# boost.net
KiCad netlist of a schematic drawn in Altium Designer
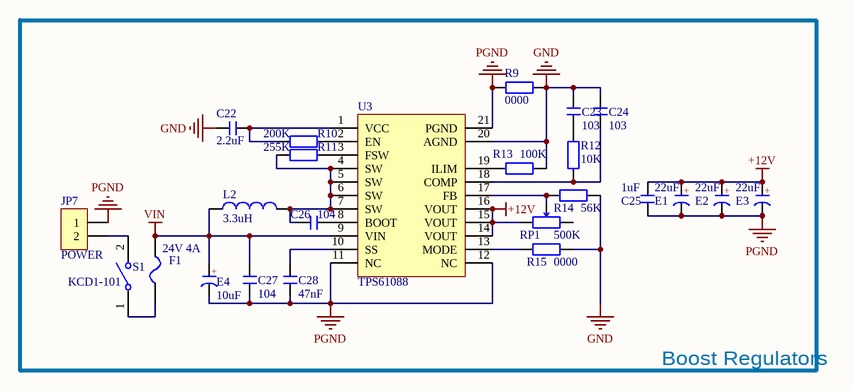
[diagram p0: boost.SchDoc]

(export (version "E")
  (design (tool "Eeschema 10.0.6"))
  (components
    (comp (ref "C22")
      (value "2.2uF")
      (footprint "C 0603_L")
      (description "无极性贴片电容")
      (fields (field (name "版权归属") "源创客"))
      (libsource (lib "3.1   - 电阻-电容-电感") (part "C"))
    )
    (comp (ref "C23")
      (value "103")
      (footprint "C 0603_L")
      (description "无极性贴片电容")
      (fields (field (name "版权归属") "源创客"))
      (libsource (lib "3.1   - 电阻-电容-电感") (part "C"))
    )
    (comp (ref "C24")
      (value "103")
      (footprint "C 0603_L")
      (description "无极性贴片电容")
      (fields (field (name "版权归属") "源创客"))
      (libsource (lib "3.1   - 电阻-电容-电感") (part "C"))
    )
    (comp (ref "C25")
      (value "1uF")
      (footprint "C 0603_L")
      (description "无极性贴片电容")
      (fields (field (name "版权归属") "源创客"))
      (libsource (lib "3.1   - 电阻-电容-电感") (part "C"))
    )
    (comp (ref "C26")
      (value "104")
      (footprint "C 0603_L")
      (description "无极性贴片电容")
      (fields (field (name "版权归属") "源创客"))
      (libsource (lib "3.1   - 电阻-电容-电感") (part "C"))
    )
    (comp (ref "C27")
      (value "104")
      (footprint "C 0603_L")
      (description "无极性贴片电容")
      (fields (field (name "版权归属") "源创客"))
      (libsource (lib "3.1   - 电阻-电容-电感") (part "C"))
    )
    (comp (ref "C28")
      (value "47nF")
      (footprint "C 0603_L")
      (description "无极性贴片电容")
      (fields (field (name "版权归属") "源创客"))
      (libsource (lib "3.1   - 电阻-电容-电感") (part "C"))
    )
    (comp (ref "E1")
      (value "22uF")
      (footprint "CD A(3216)")
      (description "贴片钽电容")
      (fields (field (name "版权归属") "源创客"))
      (libsource (lib "3.1   - 电阻-电容-电感") (part "C-CD"))
    )
    (comp (ref "E2")
      (value "22uF")
      (footprint "CD A(3216)")
      (description "贴片钽电容")
      (fields (field (name "版权归属") "源创客"))
      (libsource (lib "3.1   - 电阻-电容-电感") (part "C-CD"))
    )
    (comp (ref "E3")
      (value "22uF")
      (footprint "CD A(3216)")
      (description "贴片钽电容")
      (fields (field (name "版权归属") "源创客"))
      (libsource (lib "3.1   - 电阻-电容-电感") (part "C-CD"))
    )
    (comp (ref "E4")
      (value "10uF")
      (footprint "CD A(3216)")
      (description "贴片钽电容")
      (fields (field (name "版权归属") "源创客"))
      (libsource (lib "3.1   - 电阻-电容-电感") (part "C-CD"))
    )
    (comp (ref "F1")
      (value "24V 4A")
      (footprint "FU 1206")
      (description "贴片保险丝")
      (fields (field (name "版权归属") "源创客"))
      (libsource (lib "10.1 - 保险丝-晶振") (part "FU"))
    )
    (comp (ref "JP7")
      (value "POWER")
      (footprint "KF301-5.0-2P")
      (description "2P接插件")
      (fields (field (name "版权归属") "源创客"))
      (libsource (lib "4.10 - 接插件-脚距5.08") (part "Header 2"))
    )
    (comp (ref "L2")
      (value "3.3uH")
      (footprint "CDRH127")
      (description "Inductor")
      (fields (field (name "PUBLISHER") "Altium Limited"))
      (libsource (lib "Miscellaneous Devices") (part "Inductor"))
    )
    (comp (ref "R9")
      (value "0000")
      (footprint "R 0603_L")
      (description "贴片电阻")
      (fields (field (name "版权归属") "源创客"))
      (libsource (lib "3.1   - 电阻-电容-电感") (part "R"))
    )
    (comp (ref "R10")
      (value "200K")
      (footprint "R 0603_L")
      (description "贴片电阻")
      (fields (field (name "版权归属") "源创客"))
      (libsource (lib "3.1   - 电阻-电容-电感") (part "R"))
    )
    (comp (ref "R11")
      (value "255K")
      (footprint "R 0603_L")
      (description "贴片电阻")
      (fields (field (name "版权归属") "源创客"))
      (libsource (lib "3.1   - 电阻-电容-电感") (part "R"))
    )
    (comp (ref "R12")
      (value "10K")
      (footprint "R 0603_L")
      (description "贴片电阻")
      (fields (field (name "版权归属") "源创客"))
      (libsource (lib "3.1   - 电阻-电容-电感") (part "R"))
    )
    (comp (ref "R13")
      (value "100K")
      (footprint "R 0603_L")
      (description "贴片电阻")
      (fields (field (name "版权归属") "源创客"))
      (libsource (lib "3.1   - 电阻-电容-电感") (part "R"))
    )
    (comp (ref "R14")
      (value "56K")
      (footprint "R 0603_L")
      (description "贴片电阻")
      (fields (field (name "版权归属") "源创客"))
      (libsource (lib "3.1   - 电阻-电容-电感") (part "R"))
    )
    (comp (ref "R15")
      (value "0000")
      (footprint "R 0603_L")
      (description "贴片电阻")
      (fields (field (name "版权归属") "源创客"))
      (libsource (lib "3.1   - 电阻-电容-电感") (part "R"))
    )
    (comp (ref "RP1")
      (value "500K")
      (footprint "3296W")
      (description "插件单联电位器")
      (fields (field (name "版权归属") "源创客"))
      (libsource (lib "3.1   - 电阻-电容-电感") (part "RP-ID"))
    )
    (comp (ref "S1")
      (value "KCD1-101")
      (footprint "KCD1-101")
      (description "1路单刀船型开关")
      (fields (field (name "版权归属") "源创客"))
      (libsource (lib "5.1   - 按键-开关") (part "KCD1-101"))
    )
    (comp (ref "U3")
      (value "TPS61088")
      (footprint "S-PVQFN-N20")
      (libsource (lib "TPS61088") (part "TPS61088"))
    )
  )
  (nets
    (net (code "1") (name "+12V") (class "Default")
      (node (ref "C25") (pin "2") (pinfunction "2_2") (pintype "passive"))
      (node (ref "E1") (pin "1") (pinfunction "A_1") (pintype "passive"))
      (node (ref "E2") (pin "1") (pinfunction "A_1") (pintype "passive"))
      (node (ref "E3") (pin "1") (pinfunction "A_1") (pintype "passive"))
      (node (ref "RP1") (pin "1") (pinfunction "1_1") (pintype "passive"))
      (node (ref "U3") (pin "14") (pinfunction "VOUT_14") (pintype "passive"))
      (node (ref "U3") (pin "15") (pinfunction "VOUT_15") (pintype "passive"))
      (node (ref "U3") (pin "16") (pinfunction "VOUT_16") (pintype "passive"))
    )
    (net (code "2") (name "GND") (class "Default")
      (node (ref "C22") (pin "2") (pinfunction "2_2") (pintype "passive"))
      (node (ref "C23") (pin "2") (pinfunction "2_2") (pintype "passive"))
      (node (ref "C24") (pin "2") (pinfunction "2_2") (pintype "passive"))
      (node (ref "R13") (pin "2") (pinfunction "2_2") (pintype "passive"))
      (node (ref "R14") (pin "1") (pinfunction "1_1") (pintype "passive"))
      (node (ref "R15") (pin "2") (pinfunction "2_2") (pintype "passive"))
      (node (ref "R9") (pin "2") (pinfunction "2_2") (pintype "passive"))
      (node (ref "U3") (pin "20") (pinfunction "AGND_20") (pintype "passive"))
    )
    (net (code "3") (name "Net-(C23-Pad1)") (class "Default")
      (node (ref "C23") (pin "1") (pinfunction "1_1") (pintype "passive"))
      (node (ref "R12") (pin "2") (pinfunction "2_2") (pintype "passive"))
    )
    (net (code "4") (name "Net-(C26-Pad2)") (class "Default")
      (node (ref "C26") (pin "2") (pinfunction "2_2") (pintype "passive"))
      (node (ref "L2") (pin "2") (pinfunction "2_2") (pintype "passive"))
      (node (ref "R11") (pin "2") (pinfunction "2_2") (pintype "passive"))
      (node (ref "U3") (pin "4") (pinfunction "SW_4") (pintype "passive"))
      (node (ref "U3") (pin "5") (pinfunction "SW_5") (pintype "passive"))
      (node (ref "U3") (pin "6") (pinfunction "SW_6") (pintype "passive"))
      (node (ref "U3") (pin "7") (pinfunction "SW_7") (pintype "passive"))
    )
    (net (code "5") (name "Net-(F1-Pad1)") (class "Default")
      (node (ref "F1") (pin "1") (pinfunction "1_1") (pintype "passive"))
      (node (ref "S1") (pin "1") (pinfunction "1_1") (pintype "passive"))
    )
    (net (code "6") (name "Net-(JP7-Pad2)") (class "Default")
      (node (ref "JP7") (pin "2") (pinfunction "2_2") (pintype "passive"))
      (node (ref "S1") (pin "2") (pinfunction "2_2") (pintype "passive"))
    )
    (net (code "7") (name "Net-(U3-BOOT)") (class "Default")
      (node (ref "C26") (pin "1") (pinfunction "1_1") (pintype "passive"))
      (node (ref "U3") (pin "8") (pinfunction "BOOT_8") (pintype "passive"))
    )
    (net (code "8") (name "Net-(U3-COMP)") (class "Default")
      (node (ref "C24") (pin "1") (pinfunction "1_1") (pintype "passive"))
      (node (ref "R12") (pin "1") (pinfunction "1_1") (pintype "passive"))
      (node (ref "U3") (pin "18") (pinfunction "COMP_18") (pintype "passive"))
    )
    (net (code "9") (name "Net-(U3-EN)") (class "Default")
      (node (ref "R10") (pin "1") (pinfunction "1_1") (pintype "passive"))
      (node (ref "U3") (pin "2") (pinfunction "EN_2") (pintype "passive"))
    )
    (net (code "10") (name "Net-(U3-FB)") (class "Default")
      (node (ref "R14") (pin "2") (pinfunction "2_2") (pintype "passive"))
      (node (ref "RP1") (pin "2") (pinfunction "2_2") (pintype "passive"))
      (node (ref "U3") (pin "17") (pinfunction "FB_17") (pintype "passive"))
    )
    (net (code "11") (name "Net-(U3-FSW)") (class "Default")
      (node (ref "R11") (pin "1") (pinfunction "1_1") (pintype "passive"))
      (node (ref "U3") (pin "3") (pinfunction "FSW_3") (pintype "passive"))
    )
    (net (code "12") (name "Net-(U3-ILIM)") (class "Default")
      (node (ref "R13") (pin "1") (pinfunction "1_1") (pintype "passive"))
      (node (ref "U3") (pin "19") (pinfunction "ILIM_19") (pintype "passive"))
    )
    (net (code "13") (name "Net-(U3-MODE)") (class "Default")
      (node (ref "R15") (pin "1") (pinfunction "1_1") (pintype "passive"))
      (node (ref "U3") (pin "13") (pinfunction "MODE_13") (pintype "passive"))
    )
    (net (code "14") (name "Net-(U3-SS)") (class "Default")
      (node (ref "C28") (pin "2") (pinfunction "2_2") (pintype "passive"))
      (node (ref "U3") (pin "10") (pinfunction "SS_10") (pintype "passive"))
    )
    (net (code "15") (name "Net-(U3-VCC)") (class "Default")
      (node (ref "C22") (pin "1") (pinfunction "1_1") (pintype "passive"))
      (node (ref "R10") (pin "2") (pinfunction "2_2") (pintype "passive"))
      (node (ref "U3") (pin "1") (pinfunction "VCC_1") (pintype "passive"))
    )
    (net (code "16") (name "PGND") (class "Default")
      (node (ref "C25") (pin "1") (pinfunction "1_1") (pintype "passive"))
      (node (ref "C27") (pin "1") (pinfunction "1_1") (pintype "passive"))
      (node (ref "C28") (pin "1") (pinfunction "1_1") (pintype "passive"))
      (node (ref "E1") (pin "2") (pinfunction "K_2") (pintype "passive"))
      (node (ref "E2") (pin "2") (pinfunction "K_2") (pintype "passive"))
      (node (ref "E3") (pin "2") (pinfunction "K_2") (pintype "passive"))
      (node (ref "E4") (pin "2") (pinfunction "K_2") (pintype "passive"))
      (node (ref "JP7") (pin "1") (pinfunction "1_1") (pintype "passive"))
      (node (ref "R9") (pin "1") (pinfunction "1_1") (pintype "passive"))
      (node (ref "U3") (pin "11") (pinfunction "NC_11") (pintype "passive"))
      (node (ref "U3") (pin "12") (pinfunction "NC_12") (pintype "passive"))
      (node (ref "U3") (pin "21") (pinfunction "PGND_21") (pintype "passive"))
    )
    (net (code "17") (name "VIN") (class "Default")
      (node (ref "C27") (pin "2") (pinfunction "2_2") (pintype "passive"))
      (node (ref "E4") (pin "1") (pinfunction "A_1") (pintype "passive"))
      (node (ref "F1") (pin "2") (pinfunction "2_2") (pintype "passive"))
      (node (ref "L2") (pin "1") (pinfunction "1_1") (pintype "passive"))
      (node (ref "U3") (pin "9") (pinfunction "VIN_9") (pintype "passive"))
    )
    (net (code "18") (name "unconnected-(RP1-Pad3)") (class "Default")
      (node (ref "RP1") (pin "3") (pinfunction "3_3") (pintype "passive"))
    )
  )
)
